# Analog.net
KiCad netlist of a schematic drawn in Altium Designer
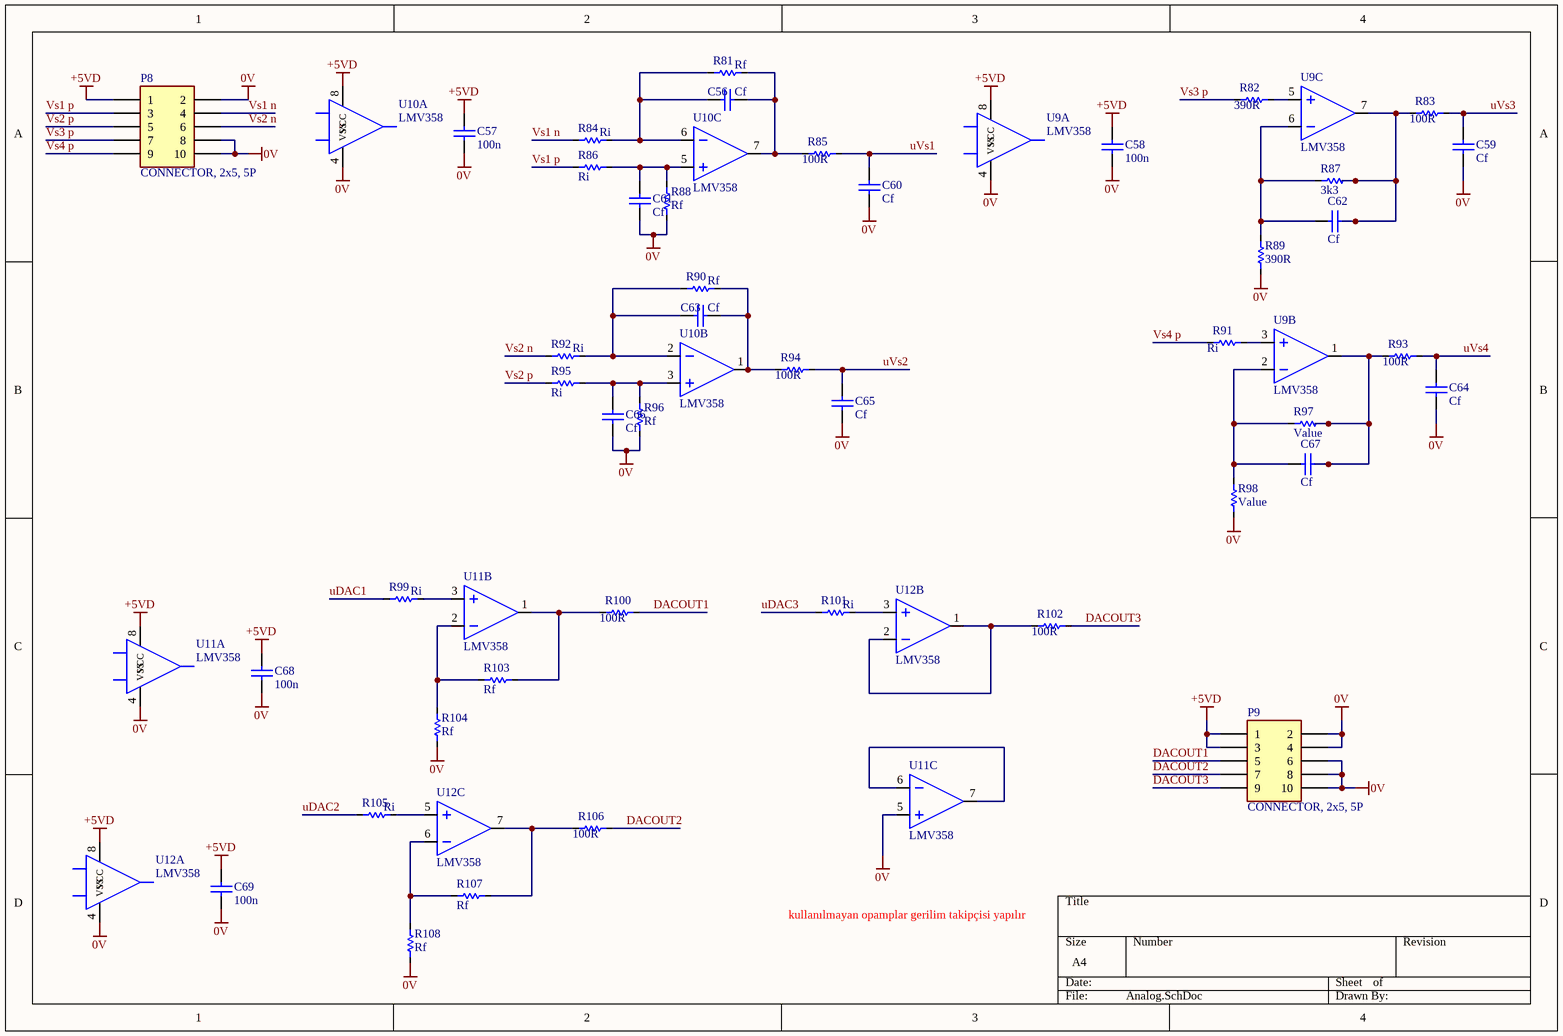
[diagram p0: Analog.SchDoc]

(export (version "E")
  (design (tool "Eeschema 10.0.6"))
  (components
    (comp (ref "C56")
      (value "Cf")
      (footprint "CC3216-1206L")
      (description "Capacitor")
      (libsource (lib "SchLibrary") (part "CAPACITOR NON-POL"))
    )
    (comp (ref "C57")
      (value "100n")
      (footprint "CC3216-1206L")
      (description "Capacitor")
      (libsource (lib "SchLibrary") (part "CAPACITOR NON-POL"))
    )
    (comp (ref "C58")
      (value "100n")
      (footprint "CC3216-1206L")
      (description "Capacitor")
      (libsource (lib "SchLibrary") (part "CAPACITOR NON-POL"))
    )
    (comp (ref "C59")
      (value "Cf")
      (footprint "CC3216-1206L")
      (description "Capacitor")
      (libsource (lib "SchLibrary") (part "CAPACITOR NON-POL"))
    )
    (comp (ref "C60")
      (value "Cf")
      (footprint "CC3216-1206L")
      (description "Capacitor")
      (libsource (lib "SchLibrary") (part "CAPACITOR NON-POL"))
    )
    (comp (ref "C61")
      (value "Cf")
      (footprint "CC3216-1206L")
      (description "Capacitor")
      (libsource (lib "SchLibrary") (part "CAPACITOR NON-POL"))
    )
    (comp (ref "C62")
      (value "Cf")
      (footprint "CC3216-1206L")
      (description "Capacitor")
      (libsource (lib "SchLibrary") (part "CAPACITOR NON-POL"))
    )
    (comp (ref "C63")
      (value "Cf")
      (footprint "CC3216-1206L")
      (description "Capacitor")
      (libsource (lib "SchLibrary") (part "CAPACITOR NON-POL"))
    )
    (comp (ref "C64")
      (value "Cf")
      (footprint "CC3216-1206L")
      (description "Capacitor")
      (libsource (lib "SchLibrary") (part "CAPACITOR NON-POL"))
    )
    (comp (ref "C65")
      (value "Cf")
      (footprint "CC3216-1206L")
      (description "Capacitor")
      (libsource (lib "SchLibrary") (part "CAPACITOR NON-POL"))
    )
    (comp (ref "C66")
      (value "Cf")
      (footprint "CC3216-1206L")
      (description "Capacitor")
      (libsource (lib "SchLibrary") (part "CAPACITOR NON-POL"))
    )
    (comp (ref "C67")
      (value "Cf")
      (footprint "CC3216-1206L")
      (description "Capacitor")
      (libsource (lib "SchLibrary") (part "CAPACITOR NON-POL"))
    )
    (comp (ref "C68")
      (value "100n")
      (footprint "CC3216-1206L")
      (description "Capacitor")
      (libsource (lib "SchLibrary") (part "CAPACITOR NON-POL"))
    )
    (comp (ref "C69")
      (value "100n")
      (footprint "CC3216-1206L")
      (description "Capacitor")
      (libsource (lib "SchLibrary") (part "CAPACITOR NON-POL"))
    )
    (comp (ref "P8")
      (value "CONNECTOR, 2x5, 5P")
      (footprint "HDR_MALE_2X5_10P_2.54MM_180")
      (description "CONNECTOR, 2x5, 10P")
      (libsource (lib "SchLibrary") (part "CONNECTOR, 2x5, 10P"))
    )
    (comp (ref "P9")
      (value "CONNECTOR, 2x5, 5P")
      (footprint "HDR_MALE_2X5_10P_2.54MM_180")
      (description "CONNECTOR, 2x5, 10P")
      (libsource (lib "SchLibrary") (part "CONNECTOR, 2x5, 10P"))
    )
    (comp (ref "R81")
      (value "Rf")
      (footprint "CR3216-1206l")
      (description "Resistor")
      (libsource (lib "SchLibrary") (part "RESISTOR"))
    )
    (comp (ref "R82")
      (value "390R")
      (footprint "CR3216-1206l")
      (description "Resistor")
      (libsource (lib "SchLibrary") (part "RESISTOR"))
    )
    (comp (ref "R83")
      (value "100R")
      (footprint "CR3216-1206l")
      (description "Resistor")
      (libsource (lib "SchLibrary") (part "RESISTOR"))
    )
    (comp (ref "R84")
      (value "Ri")
      (footprint "CR3216-1206l")
      (description "Resistor")
      (libsource (lib "SchLibrary") (part "RESISTOR"))
    )
    (comp (ref "R85")
      (value "100R")
      (footprint "CR3216-1206l")
      (description "Resistor")
      (libsource (lib "SchLibrary") (part "RESISTOR"))
    )
    (comp (ref "R86")
      (value "Ri")
      (footprint "CR3216-1206l")
      (description "Resistor")
      (libsource (lib "SchLibrary") (part "RESISTOR"))
    )
    (comp (ref "R87")
      (value "3k3")
      (footprint "CR3216-1206l")
      (description "Resistor")
      (libsource (lib "SchLibrary") (part "RESISTOR"))
    )
    (comp (ref "R88")
      (value "Rf")
      (footprint "CR3216-1206l")
      (description "Resistor")
      (libsource (lib "SchLibrary") (part "RESISTOR"))
    )
    (comp (ref "R89")
      (value "390R")
      (footprint "CR3216-1206l")
      (description "Resistor")
      (libsource (lib "SchLibrary") (part "RESISTOR"))
    )
    (comp (ref "R90")
      (value "Rf")
      (footprint "CR3216-1206l")
      (description "Resistor")
      (libsource (lib "SchLibrary") (part "RESISTOR"))
    )
    (comp (ref "R91")
      (value "Ri")
      (footprint "CR3216-1206l")
      (description "Resistor")
      (libsource (lib "SchLibrary") (part "RESISTOR"))
    )
    (comp (ref "R92")
      (value "Ri")
      (footprint "CR3216-1206l")
      (description "Resistor")
      (libsource (lib "SchLibrary") (part "RESISTOR"))
    )
    (comp (ref "R93")
      (value "100R")
      (footprint "CR3216-1206l")
      (description "Resistor")
      (libsource (lib "SchLibrary") (part "RESISTOR"))
    )
    (comp (ref "R94")
      (value "100R")
      (footprint "CR3216-1206l")
      (description "Resistor")
      (libsource (lib "SchLibrary") (part "RESISTOR"))
    )
    (comp (ref "R95")
      (value "Ri")
      (footprint "CR3216-1206l")
      (description "Resistor")
      (libsource (lib "SchLibrary") (part "RESISTOR"))
    )
    (comp (ref "R96")
      (value "Rf")
      (footprint "CR3216-1206l")
      (description "Resistor")
      (libsource (lib "SchLibrary") (part "RESISTOR"))
    )
    (comp (ref "R97")
      (value "Value")
      (footprint "CR3216-1206l")
      (description "Resistor")
      (libsource (lib "SchLibrary") (part "RESISTOR"))
    )
    (comp (ref "R98")
      (value "Value")
      (footprint "CR3216-1206l")
      (description "Resistor")
      (libsource (lib "SchLibrary") (part "RESISTOR"))
    )
    (comp (ref "R99")
      (value "Ri")
      (footprint "CR3216-1206l")
      (description "Resistor")
      (libsource (lib "SchLibrary") (part "RESISTOR"))
    )
    (comp (ref "R100")
      (value "100R")
      (footprint "CR3216-1206l")
      (description "Resistor")
      (libsource (lib "SchLibrary") (part "RESISTOR"))
    )
    (comp (ref "R101")
      (value "Ri")
      (footprint "CR3216-1206l")
      (description "Resistor")
      (libsource (lib "SchLibrary") (part "RESISTOR"))
    )
    (comp (ref "R102")
      (value "100R")
      (footprint "CR3216-1206l")
      (description "Resistor")
      (libsource (lib "SchLibrary") (part "RESISTOR"))
    )
    (comp (ref "R103")
      (value "Rf")
      (footprint "CR3216-1206l")
      (description "Resistor")
      (libsource (lib "SchLibrary") (part "RESISTOR"))
    )
    (comp (ref "R104")
      (value "Rf")
      (footprint "CR3216-1206l")
      (description "Resistor")
      (libsource (lib "SchLibrary") (part "RESISTOR"))
    )
    (comp (ref "R105")
      (value "Ri")
      (footprint "CR3216-1206l")
      (description "Resistor")
      (libsource (lib "SchLibrary") (part "RESISTOR"))
    )
    (comp (ref "R106")
      (value "100R")
      (footprint "CR3216-1206l")
      (description "Resistor")
      (libsource (lib "SchLibrary") (part "RESISTOR"))
    )
    (comp (ref "R107")
      (value "Rf")
      (footprint "CR3216-1206l")
      (description "Resistor")
      (libsource (lib "SchLibrary") (part "RESISTOR"))
    )
    (comp (ref "R108")
      (value "Rf")
      (footprint "CR3216-1206l")
      (description "Resistor")
      (libsource (lib "SchLibrary") (part "RESISTOR"))
    )
    (comp (ref "U9")
      (value "LMV358")
      (footprint "SOIC127P600X175-8N")
      (description "Dual Opamp")
      (libsource (lib "SchLibrary") (part "OPAMP2"))
    )
    (comp (ref "U10")
      (value "LMV358")
      (footprint "SOIC127P600X175-8N")
      (description "Dual Opamp")
      (libsource (lib "SchLibrary") (part "OPAMP2"))
    )
    (comp (ref "U11")
      (value "LMV358")
      (footprint "SOIC127P600X175-8N")
      (description "Dual Opamp")
      (libsource (lib "SchLibrary") (part "OPAMP2"))
    )
    (comp (ref "U12")
      (value "LMV358")
      (footprint "SOIC127P600X175-8N")
      (description "Dual Opamp")
      (libsource (lib "SchLibrary") (part "OPAMP2"))
    )
  )
  (nets
    (net (code "1") (name "+5VD") (class "Default")
      (node (ref "C57") (pin "1") (pintype "passive"))
      (node (ref "C58") (pin "1") (pintype "passive"))
      (node (ref "C68") (pin "1") (pintype "passive"))
      (node (ref "C69") (pin "1") (pintype "passive"))
      (node (ref "P8") (pin "1") (pinfunction "1_1") (pintype "passive"))
      (node (ref "P9") (pin "1") (pinfunction "1_1") (pintype "passive"))
      (node (ref "P9") (pin "3") (pinfunction "3_3") (pintype "passive"))
      (node (ref "U10") (pin "8") (pinfunction "VCC_8") (pintype "passive"))
      (node (ref "U11") (pin "8") (pinfunction "VCC_8") (pintype "passive"))
      (node (ref "U12") (pin "8") (pinfunction "VCC_8") (pintype "passive"))
      (node (ref "U9") (pin "8") (pinfunction "VCC_8") (pintype "passive"))
    )
    (net (code "2") (name "/DACOUT1") (class "Default")
      (node (ref "P9") (pin "5") (pinfunction "5_5") (pintype "passive"))
      (node (ref "R100") (pin "2") (pinfunction "2_2") (pintype "passive"))
    )
    (net (code "3") (name "/DACOUT2") (class "Default")
      (node (ref "P9") (pin "7") (pinfunction "7_7") (pintype "passive"))
      (node (ref "R106") (pin "2") (pinfunction "2_2") (pintype "passive"))
    )
    (net (code "4") (name "/DACOUT3") (class "Default")
      (node (ref "P9") (pin "9") (pinfunction "9_9") (pintype "passive"))
      (node (ref "R102") (pin "2") (pinfunction "2_2") (pintype "passive"))
    )
    (net (code "5") (name "/Vs1 n") (class "Default")
      (node (ref "P8") (pin "4") (pinfunction "4_4") (pintype "passive"))
      (node (ref "R84") (pin "1") (pinfunction "1_1") (pintype "passive"))
    )
    (net (code "6") (name "/Vs1 p") (class "Default")
      (node (ref "P8") (pin "3") (pinfunction "3_3") (pintype "passive"))
      (node (ref "R86") (pin "1") (pinfunction "1_1") (pintype "passive"))
    )
    (net (code "7") (name "/Vs2 n") (class "Default")
      (node (ref "P8") (pin "6") (pinfunction "6_6") (pintype "passive"))
      (node (ref "R92") (pin "1") (pinfunction "1_1") (pintype "passive"))
    )
    (net (code "8") (name "/Vs2 p") (class "Default")
      (node (ref "P8") (pin "5") (pinfunction "5_5") (pintype "passive"))
      (node (ref "R95") (pin "1") (pinfunction "1_1") (pintype "passive"))
    )
    (net (code "9") (name "/Vs3 p") (class "Default")
      (node (ref "P8") (pin "7") (pinfunction "7_7") (pintype "passive"))
      (node (ref "R82") (pin "1") (pinfunction "1_1") (pintype "passive"))
    )
    (net (code "10") (name "/Vs4 p") (class "Default")
      (node (ref "P8") (pin "9") (pinfunction "9_9") (pintype "passive"))
      (node (ref "R91") (pin "1") (pinfunction "1_1") (pintype "passive"))
    )
    (net (code "11") (name "/uDAC1") (class "Default")
      (node (ref "R99") (pin "1") (pinfunction "1_1") (pintype "passive"))
    )
    (net (code "12") (name "/uDAC2") (class "Default")
      (node (ref "R105") (pin "1") (pinfunction "1_1") (pintype "passive"))
    )
    (net (code "13") (name "/uDAC3") (class "Default")
      (node (ref "R101") (pin "1") (pinfunction "1_1") (pintype "passive"))
    )
    (net (code "14") (name "/uVs1") (class "Default")
      (node (ref "C60") (pin "1") (pintype "passive"))
      (node (ref "R85") (pin "2") (pinfunction "2_2") (pintype "passive"))
    )
    (net (code "15") (name "/uVs2") (class "Default")
      (node (ref "C65") (pin "1") (pintype "passive"))
      (node (ref "R94") (pin "2") (pinfunction "2_2") (pintype "passive"))
    )
    (net (code "16") (name "/uVs3") (class "Default")
      (node (ref "C59") (pin "2") (pintype "passive"))
      (node (ref "R83") (pin "2") (pinfunction "2_2") (pintype "passive"))
    )
    (net (code "17") (name "/uVs4") (class "Default")
      (node (ref "C64") (pin "2") (pintype "passive"))
      (node (ref "R93") (pin "2") (pinfunction "2_2") (pintype "passive"))
    )
    (net (code "18") (name "0V") (class "Default")
      (node (ref "C57") (pin "2") (pintype "passive"))
      (node (ref "C58") (pin "2") (pintype "passive"))
      (node (ref "C59") (pin "1") (pintype "passive"))
      (node (ref "C60") (pin "2") (pintype "passive"))
      (node (ref "C61") (pin "2") (pintype "passive"))
      (node (ref "C64") (pin "1") (pintype "passive"))
      (node (ref "C65") (pin "2") (pintype "passive"))
      (node (ref "C66") (pin "2") (pintype "passive"))
      (node (ref "C68") (pin "2") (pintype "passive"))
      (node (ref "C69") (pin "2") (pintype "passive"))
      (node (ref "P8") (pin "10") (pinfunction "10_10") (pintype "passive"))
      (node (ref "P8") (pin "2") (pinfunction "2_2") (pintype "passive"))
      (node (ref "P8") (pin "8") (pinfunction "8_8") (pintype "passive"))
      (node (ref "P9") (pin "10") (pinfunction "10_10") (pintype "passive"))
      (node (ref "P9") (pin "2") (pinfunction "2_2") (pintype "passive"))
      (node (ref "P9") (pin "4") (pinfunction "4_4") (pintype "passive"))
      (node (ref "P9") (pin "6") (pinfunction "6_6") (pintype "passive"))
      (node (ref "P9") (pin "8") (pinfunction "8_8") (pintype "passive"))
      (node (ref "R104") (pin "1") (pinfunction "1_1") (pintype "passive"))
      (node (ref "R108") (pin "1") (pinfunction "1_1") (pintype "passive"))
      (node (ref "R88") (pin "1") (pinfunction "1_1") (pintype "passive"))
      (node (ref "R89") (pin "2") (pinfunction "2_2") (pintype "passive"))
      (node (ref "R96") (pin "1") (pinfunction "1_1") (pintype "passive"))
      (node (ref "R98") (pin "2") (pinfunction "2_2") (pintype "passive"))
      (node (ref "U10") (pin "4") (pinfunction "VSS_4") (pintype "passive"))
      (node (ref "U11") (pin "4") (pinfunction "VSS_4") (pintype "passive"))
      (node (ref "U11") (pin "5") (pinfunction "5_5") (pintype "passive"))
      (node (ref "U12") (pin "4") (pinfunction "VSS_4") (pintype "passive"))
      (node (ref "U9") (pin "4") (pinfunction "VSS_4") (pintype "passive"))
    )
    (net (code "19") (name "Net-(C56-Pad1)") (class "Default")
      (node (ref "C56") (pin "1") (pintype "passive"))
      (node (ref "R81") (pin "1") (pinfunction "1_1") (pintype "passive"))
      (node (ref "R84") (pin "2") (pinfunction "2_2") (pintype "passive"))
      (node (ref "U10") (pin "6") (pinfunction "6_6") (pintype "passive"))
    )
    (net (code "20") (name "Net-(C56-Pad2)") (class "Default")
      (node (ref "C56") (pin "2") (pintype "passive"))
      (node (ref "R81") (pin "2") (pinfunction "2_2") (pintype "passive"))
      (node (ref "R85") (pin "1") (pinfunction "1_1") (pintype "passive"))
      (node (ref "U10") (pin "7") (pinfunction "7_7") (pintype "passive"))
    )
    (net (code "21") (name "Net-(C61-Pad1)") (class "Default")
      (node (ref "C61") (pin "1") (pintype "passive"))
      (node (ref "R86") (pin "2") (pinfunction "2_2") (pintype "passive"))
      (node (ref "R88") (pin "2") (pinfunction "2_2") (pintype "passive"))
      (node (ref "U10") (pin "5") (pinfunction "5_5") (pintype "passive"))
    )
    (net (code "22") (name "Net-(C62-Pad1)") (class "Default")
      (node (ref "C62") (pin "1") (pintype "passive"))
      (node (ref "R83") (pin "1") (pinfunction "1_1") (pintype "passive"))
      (node (ref "R87") (pin "1") (pinfunction "1_1") (pintype "passive"))
      (node (ref "U9") (pin "7") (pinfunction "7_7") (pintype "passive"))
    )
    (net (code "23") (name "Net-(C62-Pad2)") (class "Default")
      (node (ref "C62") (pin "2") (pintype "passive"))
      (node (ref "R87") (pin "2") (pinfunction "2_2") (pintype "passive"))
      (node (ref "R89") (pin "1") (pinfunction "1_1") (pintype "passive"))
      (node (ref "U9") (pin "6") (pinfunction "6_6") (pintype "passive"))
    )
    (net (code "24") (name "Net-(C63-Pad1)") (class "Default")
      (node (ref "C63") (pin "1") (pintype "passive"))
      (node (ref "R90") (pin "1") (pinfunction "1_1") (pintype "passive"))
      (node (ref "R92") (pin "2") (pinfunction "2_2") (pintype "passive"))
      (node (ref "U10") (pin "2") (pinfunction "2_2") (pintype "passive"))
    )
    (net (code "25") (name "Net-(C63-Pad2)") (class "Default")
      (node (ref "C63") (pin "2") (pintype "passive"))
      (node (ref "R90") (pin "2") (pinfunction "2_2") (pintype "passive"))
      (node (ref "R94") (pin "1") (pinfunction "1_1") (pintype "passive"))
      (node (ref "U10") (pin "1") (pinfunction "1_1") (pintype "passive"))
    )
    (net (code "26") (name "Net-(C66-Pad1)") (class "Default")
      (node (ref "C66") (pin "1") (pintype "passive"))
      (node (ref "R95") (pin "2") (pinfunction "2_2") (pintype "passive"))
      (node (ref "R96") (pin "2") (pinfunction "2_2") (pintype "passive"))
      (node (ref "U10") (pin "3") (pinfunction "3_3") (pintype "passive"))
    )
    (net (code "27") (name "Net-(C67-Pad1)") (class "Default")
      (node (ref "C67") (pin "1") (pintype "passive"))
      (node (ref "R93") (pin "1") (pinfunction "1_1") (pintype "passive"))
      (node (ref "R97") (pin "1") (pinfunction "1_1") (pintype "passive"))
      (node (ref "U9") (pin "1") (pinfunction "1_1") (pintype "passive"))
    )
    (net (code "28") (name "Net-(C67-Pad2)") (class "Default")
      (node (ref "C67") (pin "2") (pintype "passive"))
      (node (ref "R97") (pin "2") (pinfunction "2_2") (pintype "passive"))
      (node (ref "R98") (pin "1") (pinfunction "1_1") (pintype "passive"))
      (node (ref "U9") (pin "2") (pinfunction "2_2") (pintype "passive"))
    )
    (net (code "29") (name "Net-(R82-Pad2)") (class "Default")
      (node (ref "R82") (pin "2") (pinfunction "2_2") (pintype "passive"))
      (node (ref "U9") (pin "5") (pinfunction "5_5") (pintype "passive"))
    )
    (net (code "30") (name "Net-(R91-Pad2)") (class "Default")
      (node (ref "R91") (pin "2") (pinfunction "2_2") (pintype "passive"))
      (node (ref "U9") (pin "3") (pinfunction "3_3") (pintype "passive"))
    )
    (net (code "31") (name "Net-(R99-Pad2)") (class "Default")
      (node (ref "R99") (pin "2") (pinfunction "2_2") (pintype "passive"))
      (node (ref "U11") (pin "3") (pinfunction "3_3") (pintype "passive"))
    )
    (net (code "32") (name "Net-(R100-Pad1)") (class "Default")
      (node (ref "R100") (pin "1") (pinfunction "1_1") (pintype "passive"))
      (node (ref "R103") (pin "2") (pinfunction "2_2") (pintype "passive"))
      (node (ref "U11") (pin "1") (pinfunction "1_1") (pintype "passive"))
    )
    (net (code "33") (name "Net-(R101-Pad2)") (class "Default")
      (node (ref "R101") (pin "2") (pinfunction "2_2") (pintype "passive"))
      (node (ref "U12") (pin "3") (pinfunction "3_3") (pintype "passive"))
    )
    (net (code "34") (name "Net-(R102-Pad1)") (class "Default")
      (node (ref "R102") (pin "1") (pinfunction "1_1") (pintype "passive"))
      (node (ref "U12") (pin "1") (pinfunction "1_1") (pintype "passive"))
      (node (ref "U12") (pin "2") (pinfunction "2_2") (pintype "passive"))
    )
    (net (code "35") (name "Net-(R103-Pad1)") (class "Default")
      (node (ref "R103") (pin "1") (pinfunction "1_1") (pintype "passive"))
      (node (ref "R104") (pin "2") (pinfunction "2_2") (pintype "passive"))
      (node (ref "U11") (pin "2") (pinfunction "2_2") (pintype "passive"))
    )
    (net (code "36") (name "Net-(R105-Pad2)") (class "Default")
      (node (ref "R105") (pin "2") (pinfunction "2_2") (pintype "passive"))
      (node (ref "U12") (pin "5") (pinfunction "5_5") (pintype "passive"))
    )
    (net (code "37") (name "Net-(R106-Pad1)") (class "Default")
      (node (ref "R106") (pin "1") (pinfunction "1_1") (pintype "passive"))
      (node (ref "R107") (pin "2") (pinfunction "2_2") (pintype "passive"))
      (node (ref "U12") (pin "7") (pinfunction "7_7") (pintype "passive"))
    )
    (net (code "38") (name "Net-(R107-Pad1)") (class "Default")
      (node (ref "R107") (pin "1") (pinfunction "1_1") (pintype "passive"))
      (node (ref "R108") (pin "2") (pinfunction "2_2") (pintype "passive"))
      (node (ref "U12") (pin "6") (pinfunction "6_6") (pintype "passive"))
    )
    (net (code "39") (name "Net-(U11-Pad6)") (class "Default")
      (node (ref "U11") (pin "6") (pinfunction "6_6") (pintype "passive"))
      (node (ref "U11") (pin "7") (pinfunction "7_7") (pintype "passive"))
    )
  )
)
